# logic_interface.net
KiCad netlist of a schematic drawn in EAGLE
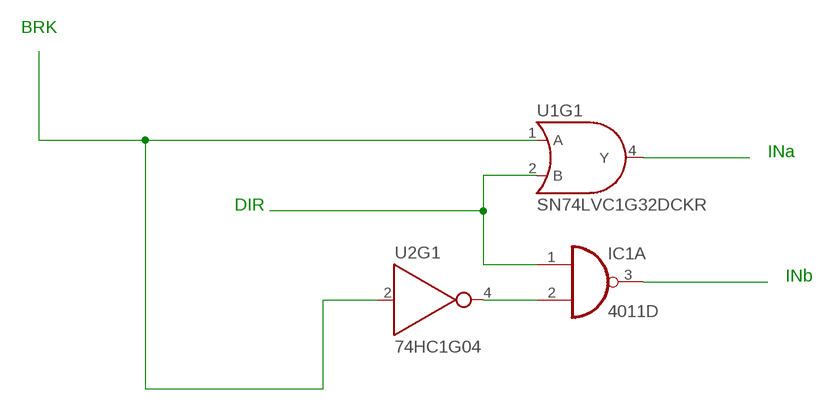
[diagram p0: schematic, sheet 1]

(export (version "E")
  (design (tool "Eeschema 10.0.6"))
  (components
    (comp (ref "IC1")
      (value "4011D")
      (footprint "eagle-import:SO14")
      (libsource (lib "eagle-import") (part "4011D"))
    )
    (comp (ref "U1")
      (value "SN74LVC1G32DCKR")
      (footprint "eagle-import:SOT23-5")
      (libsource (lib "eagle-import") (part "7432DBVLVC"))
    )
    (comp (ref "U2")
      (value "74HC1G04")
      (footprint "eagle-import:SOT353")
      (libsource (lib "eagle-import") (part "741G04HC"))
    )
  )
  (nets
    (net (code "1") (name "Net-(IC1A-I0)") (class "Default")
      (node (ref "IC1") (pin "1") (pinfunction "I0_1") (pintype "input"))
      (node (ref "U1") (pin "2") (pinfunction "B_2") (pintype "bidirectional"))
    )
    (net (code "2") (name "Net-(IC1A-I1)") (class "Default")
      (node (ref "IC1") (pin "2") (pinfunction "I1_2") (pintype "input"))
      (node (ref "U2") (pin "4") (pinfunction "Y_4") (pintype "bidirectional"))
    )
    (net (code "3") (name "Net-(U1A-A)") (class "Default")
      (node (ref "U1") (pin "1") (pinfunction "A_1") (pintype "bidirectional"))
      (node (ref "U2") (pin "2") (pinfunction "A_2") (pintype "bidirectional"))
    )
    (net (code "4") (name "unconnected-(IC1A-O-Pad3)") (class "Default")
      (node (ref "IC1") (pin "3") (pinfunction "O_3") (pintype "output"))
    )
    (net (code "5") (name "unconnected-(U1A-Y-Pad4)") (class "Default")
      (node (ref "U1") (pin "4") (pinfunction "Y_4") (pintype "bidirectional"))
    )
  )
)
